# Morpheus_MEM.net
KiCad netlist of a schematic drawn in Altium Designer
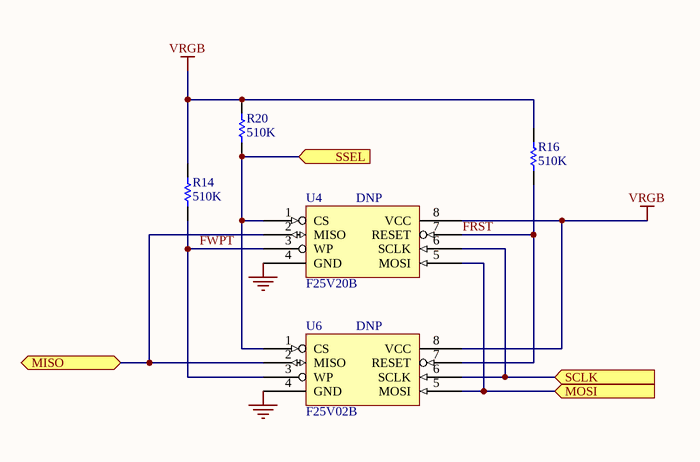
[diagram p0: Morpheus_MEM.SchDoc]

(export (version "E")
  (design (tool "Eeschema 10.0.6"))
  (components
    (comp (ref "R14")
      (value "510K")
      (footprint "RES0402")
      (description "Chip Resistor")
      (fields (field (name "TOLERANCE") "5 %") (field (name "POWER") "0.1 W"))
      (libsource (lib "Hello") (part "R_510K_5_0.1_0402"))
    )
    (comp (ref "R16")
      (value "510K")
      (footprint "RES0402")
      (description "Chip Resistor")
      (fields (field (name "TOLERANCE") "5 %") (field (name "POWER") "0.1 W"))
      (libsource (lib "Hello") (part "R_510K_5_0.1_0402"))
    )
    (comp (ref "R20")
      (value "510K")
      (footprint "RES0402")
      (description "Chip Resistor")
      (fields (field (name "TOLERANCE") "5 %") (field (name "POWER") "0.1 W"))
      (libsource (lib "Hello") (part "R_510K_5_0.1_0402"))
    )
    (comp (ref "U4")
      (value "DNP")
      (footprint "DFN127P600x500x80-8D")
      (description "Cypress SPI FRAM 256Kx8")
      (fields (field (name "PN") "F25V20B"))
      (libsource (lib "dykes") (part "FM25V20B"))
    )
    (comp (ref "U6")
      (value "DNP")
      (footprint "DFN95P500x450x80-8D")
      (description "Cypress SPI FRAM 32Kx8")
      (fields (field (name "PN") "F25V02B"))
      (libsource (lib "dykes") (part "FM25V02B"))
    )
  )
  (nets
    (net (code "1") (name "/FRST") (class "Default")
      (node (ref "R16") (pin "1") (pinfunction "1_1") (pintype "passive"))
      (node (ref "U4") (pin "7") (pinfunction "RESET_7") (pintype "input"))
      (node (ref "U6") (pin "7") (pinfunction "RESET_7") (pintype "input"))
    )
    (net (code "2") (name "/FWPT") (class "Default")
      (node (ref "R14") (pin "1") (pinfunction "1_1") (pintype "passive"))
      (node (ref "U4") (pin "3") (pinfunction "WP_3") (pintype "passive"))
      (node (ref "U6") (pin "3") (pinfunction "WP_3") (pintype "passive"))
    )
    (net (code "3") (name "/MISO") (class "Default")
      (node (ref "U4") (pin "2") (pinfunction "MISO_2") (pintype "bidirectional"))
      (node (ref "U6") (pin "2") (pinfunction "MISO_2") (pintype "bidirectional"))
    )
    (net (code "4") (name "/MOSI") (class "Default")
      (node (ref "U4") (pin "5") (pinfunction "MOSI_5") (pintype "input"))
      (node (ref "U6") (pin "5") (pinfunction "MOSI_5") (pintype "input"))
    )
    (net (code "5") (name "/SCLK") (class "Default")
      (node (ref "U4") (pin "6") (pinfunction "SCLK_6") (pintype "input"))
      (node (ref "U6") (pin "6") (pinfunction "SCLK_6") (pintype "input"))
    )
    (net (code "6") (name "/SSEL") (class "Default")
      (node (ref "R20") (pin "1") (pinfunction "1_1") (pintype "passive"))
      (node (ref "U4") (pin "1") (pinfunction "CS_1") (pintype "input"))
      (node (ref "U6") (pin "1") (pinfunction "CS_1") (pintype "input"))
    )
    (net (code "7") (name "GND") (class "Default")
      (node (ref "U4") (pin "4") (pinfunction "GND_4") (pintype "power_in"))
      (node (ref "U6") (pin "4") (pinfunction "GND_4") (pintype "power_in"))
    )
    (net (code "8") (name "VRGB") (class "Default")
      (node (ref "R14") (pin "2") (pinfunction "2_2") (pintype "passive"))
      (node (ref "R16") (pin "2") (pinfunction "2_2") (pintype "passive"))
      (node (ref "R20") (pin "2") (pinfunction "2_2") (pintype "passive"))
      (node (ref "U4") (pin "8") (pinfunction "VCC_8") (pintype "power_in"))
      (node (ref "U6") (pin "8") (pinfunction "VCC_8") (pintype "power_in"))
    )
  )
)
